# OSO-MISC-20-003_I2C_Sensors.net
KiCad netlist of a schematic drawn in EAGLE
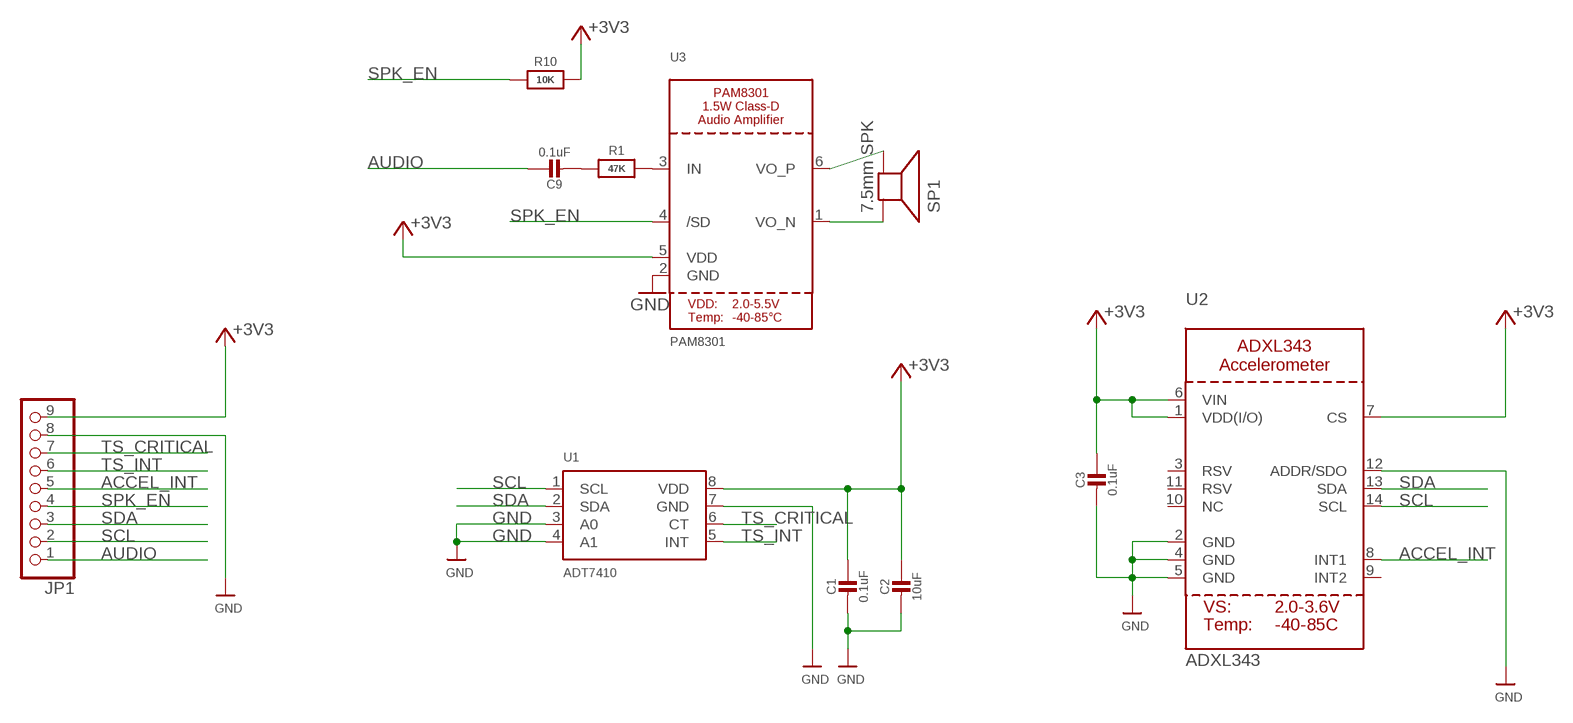
[diagram p0: schematic, sheet 1]

(export (version "E")
  (design (tool "Eeschema 10.0.6"))
  (components
    (comp (ref "C1")
      (value "0.1uF")
      (footprint "eagle-import:0805-NO")
      (libsource (lib "eagle-import") (part "CAP_CERAMIC0805-NOOUTLINE"))
    )
    (comp (ref "C2")
      (value "10uF")
      (footprint "eagle-import:0805-NO")
      (libsource (lib "eagle-import") (part "CAP_CERAMIC0805-NOOUTLINE"))
    )
    (comp (ref "C3")
      (value "0.1uF")
      (footprint "eagle-import:0805-NO")
      (libsource (lib "eagle-import") (part "CAP_CERAMIC0805-NOOUTLINE"))
    )
    (comp (ref "C9")
      (value "0.1uF")
      (footprint "eagle-import:0805-NO")
      (libsource (lib "eagle-import") (part "CAP_CERAMIC0805-NOOUTLINE"))
    )
    (comp (ref "JP1")
      (value "HEADER-1X9_JSTSH")
      (footprint "eagle-import:JST_SH9")
      (libsource (lib "eagle-import") (part "HEADER-1X9_JSTSH"))
    )
    (comp (ref "R1")
      (value "47K")
      (footprint "eagle-import:0805-NO")
      (libsource (lib "eagle-import") (part "RESISTOR0805_NOOUTLINE"))
    )
    (comp (ref "R10")
      (value "10K")
      (footprint "eagle-import:0805-NO")
      (libsource (lib "eagle-import") (part "RESISTOR0805_NOOUTLINE"))
    )
    (comp (ref "SP1")
      (value "7.5mm SPK")
      (footprint "eagle-import:BUZZER_SMT_5MM")
      (libsource (lib "eagle-import") (part "SPEAKER_BUZZER5MM"))
    )
    (comp (ref "U1")
      (value "ADT7410")
      (footprint "eagle-import:SOIC8_150MIL")
      (libsource (lib "eagle-import") (part "TEMP_ADT7410"))
    )
    (comp (ref "U2")
      (value "ADXL343")
      (footprint "eagle-import:LGA14")
      (libsource (lib "eagle-import") (part "ACCEL_ADXL343"))
    )
    (comp (ref "U3")
      (value "PAM8301")
      (footprint "eagle-import:SOT23-6")
      (libsource (lib "eagle-import") (part "PAM8301"))
    )
  )
  (nets
    (net (code "1") (name "+3V3") (class "Default")
      (node (ref "C1") (pin "1") (pinfunction "1_1") (pintype "passive"))
      (node (ref "C2") (pin "1") (pinfunction "1_1") (pintype "passive"))
      (node (ref "C3") (pin "1") (pinfunction "1_1") (pintype "passive"))
      (node (ref "JP1") (pin "9") (pinfunction "9_9") (pintype "passive"))
      (node (ref "R10") (pin "2") (pinfunction "2_2") (pintype "passive"))
      (node (ref "U1") (pin "8") (pinfunction "VDD_8") (pintype "power_in"))
      (node (ref "U2") (pin "1") (pinfunction "VDD(I/O)_1") (pintype "bidirectional"))
      (node (ref "U2") (pin "6") (pinfunction "VIN_6") (pintype "bidirectional"))
      (node (ref "U2") (pin "7") (pinfunction "CS_7") (pintype "bidirectional"))
      (node (ref "U3") (pin "5") (pinfunction "VDD_5") (pintype "power_in"))
    )
    (net (code "2") (name "/ACCEL_INT") (class "Default")
      (node (ref "JP1") (pin "5") (pinfunction "5_5") (pintype "passive"))
      (node (ref "U2") (pin "8") (pinfunction "INT1_8") (pintype "bidirectional"))
    )
    (net (code "3") (name "/AUDIO") (class "Default")
      (node (ref "C9") (pin "1") (pinfunction "1_1") (pintype "passive"))
      (node (ref "JP1") (pin "1") (pinfunction "1_1") (pintype "passive"))
    )
    (net (code "4") (name "/SCL") (class "Default")
      (node (ref "JP1") (pin "2") (pinfunction "2_2") (pintype "passive"))
      (node (ref "U1") (pin "1") (pinfunction "SCL_1") (pintype "bidirectional"))
      (node (ref "U2") (pin "14") (pinfunction "SCL_14") (pintype "bidirectional"))
    )
    (net (code "5") (name "/SDA") (class "Default")
      (node (ref "JP1") (pin "3") (pinfunction "3_3") (pintype "passive"))
      (node (ref "U1") (pin "2") (pinfunction "SDA_2") (pintype "bidirectional"))
      (node (ref "U2") (pin "13") (pinfunction "SDA_13") (pintype "bidirectional"))
    )
    (net (code "6") (name "/SPK_EN") (class "Default")
      (node (ref "JP1") (pin "4") (pinfunction "4_4") (pintype "passive"))
      (node (ref "R10") (pin "1") (pinfunction "1_1") (pintype "passive"))
      (node (ref "U3") (pin "4") (pinfunction "/SD_4") (pintype "input"))
    )
    (net (code "7") (name "/TS_CRITICAL") (class "Default")
      (node (ref "JP1") (pin "7") (pinfunction "7_7") (pintype "passive"))
      (node (ref "U1") (pin "6") (pinfunction "CT_6") (pintype "bidirectional"))
    )
    (net (code "8") (name "/TS_INT") (class "Default")
      (node (ref "JP1") (pin "6") (pinfunction "6_6") (pintype "passive"))
      (node (ref "U1") (pin "5") (pinfunction "INT_5") (pintype "bidirectional"))
    )
    (net (code "9") (name "GND") (class "Default")
      (node (ref "C1") (pin "2") (pinfunction "2_2") (pintype "passive"))
      (node (ref "C2") (pin "2") (pinfunction "2_2") (pintype "passive"))
      (node (ref "C3") (pin "2") (pinfunction "2_2") (pintype "passive"))
      (node (ref "JP1") (pin "8") (pinfunction "8_8") (pintype "passive"))
      (node (ref "U1") (pin "3") (pinfunction "A0_3") (pintype "bidirectional"))
      (node (ref "U1") (pin "4") (pinfunction "A1_4") (pintype "bidirectional"))
      (node (ref "U1") (pin "7") (pinfunction "GND_7") (pintype "power_in"))
      (node (ref "U2") (pin "12") (pinfunction "ADDR/SDO_12") (pintype "bidirectional"))
      (node (ref "U2") (pin "2") (pinfunction "GND_2") (pintype "bidirectional"))
      (node (ref "U2") (pin "4") (pinfunction "GND_4") (pintype "bidirectional"))
      (node (ref "U2") (pin "5") (pinfunction "GND_5") (pintype "bidirectional"))
      (node (ref "U3") (pin "2") (pinfunction "GND_2") (pintype "power_in"))
    )
    (net (code "10") (name "Net-(C9-Pad2)") (class "Default")
      (node (ref "C9") (pin "2") (pinfunction "2_2") (pintype "passive"))
      (node (ref "R1") (pin "1") (pinfunction "1_1") (pintype "passive"))
    )
    (net (code "11") (name "Net-(U3-IN)") (class "Default")
      (node (ref "R1") (pin "2") (pinfunction "2_2") (pintype "passive"))
      (node (ref "U3") (pin "3") (pinfunction "IN_3") (pintype "input"))
    )
    (net (code "12") (name "Net-(U3-VO_N)") (class "Default")
      (node (ref "SP1") (pin "+") (pinfunction "+_+") (pintype "passive"))
      (node (ref "U3") (pin "1") (pinfunction "VO_N_1") (pintype "output"))
    )
    (net (code "13") (name "Net-(U3-VO_P)") (class "Default")
      (node (ref "SP1") (pin "-") (pinfunction "-_-") (pintype "passive"))
      (node (ref "U3") (pin "6") (pinfunction "VO_P_6") (pintype "output"))
    )
    (net (code "14") (name "unconnected-(U2-INT2-Pad9)") (class "Default")
      (node (ref "U2") (pin "9") (pinfunction "INT2_9") (pintype "bidirectional"))
    )
    (net (code "15") (name "unconnected-(U2-NC-Pad10)") (class "Default")
      (node (ref "U2") (pin "10") (pinfunction "NC_10") (pintype "bidirectional"))
    )
    (net (code "16") (name "unconnected-(U2-RSV-Pad3)") (class "Default")
      (node (ref "U2") (pin "3") (pinfunction "RSV_3") (pintype "bidirectional"))
    )
    (net (code "17") (name "unconnected-(U2-RSV-Pad11)") (class "Default")
      (node (ref "U2") (pin "11") (pinfunction "RSV_11") (pintype "bidirectional"))
    )
  )
)
